# FMC_ADC_100M_10B_8CHA_TDC_PSU.net
KiCad netlist of a schematic drawn in Altium Designer
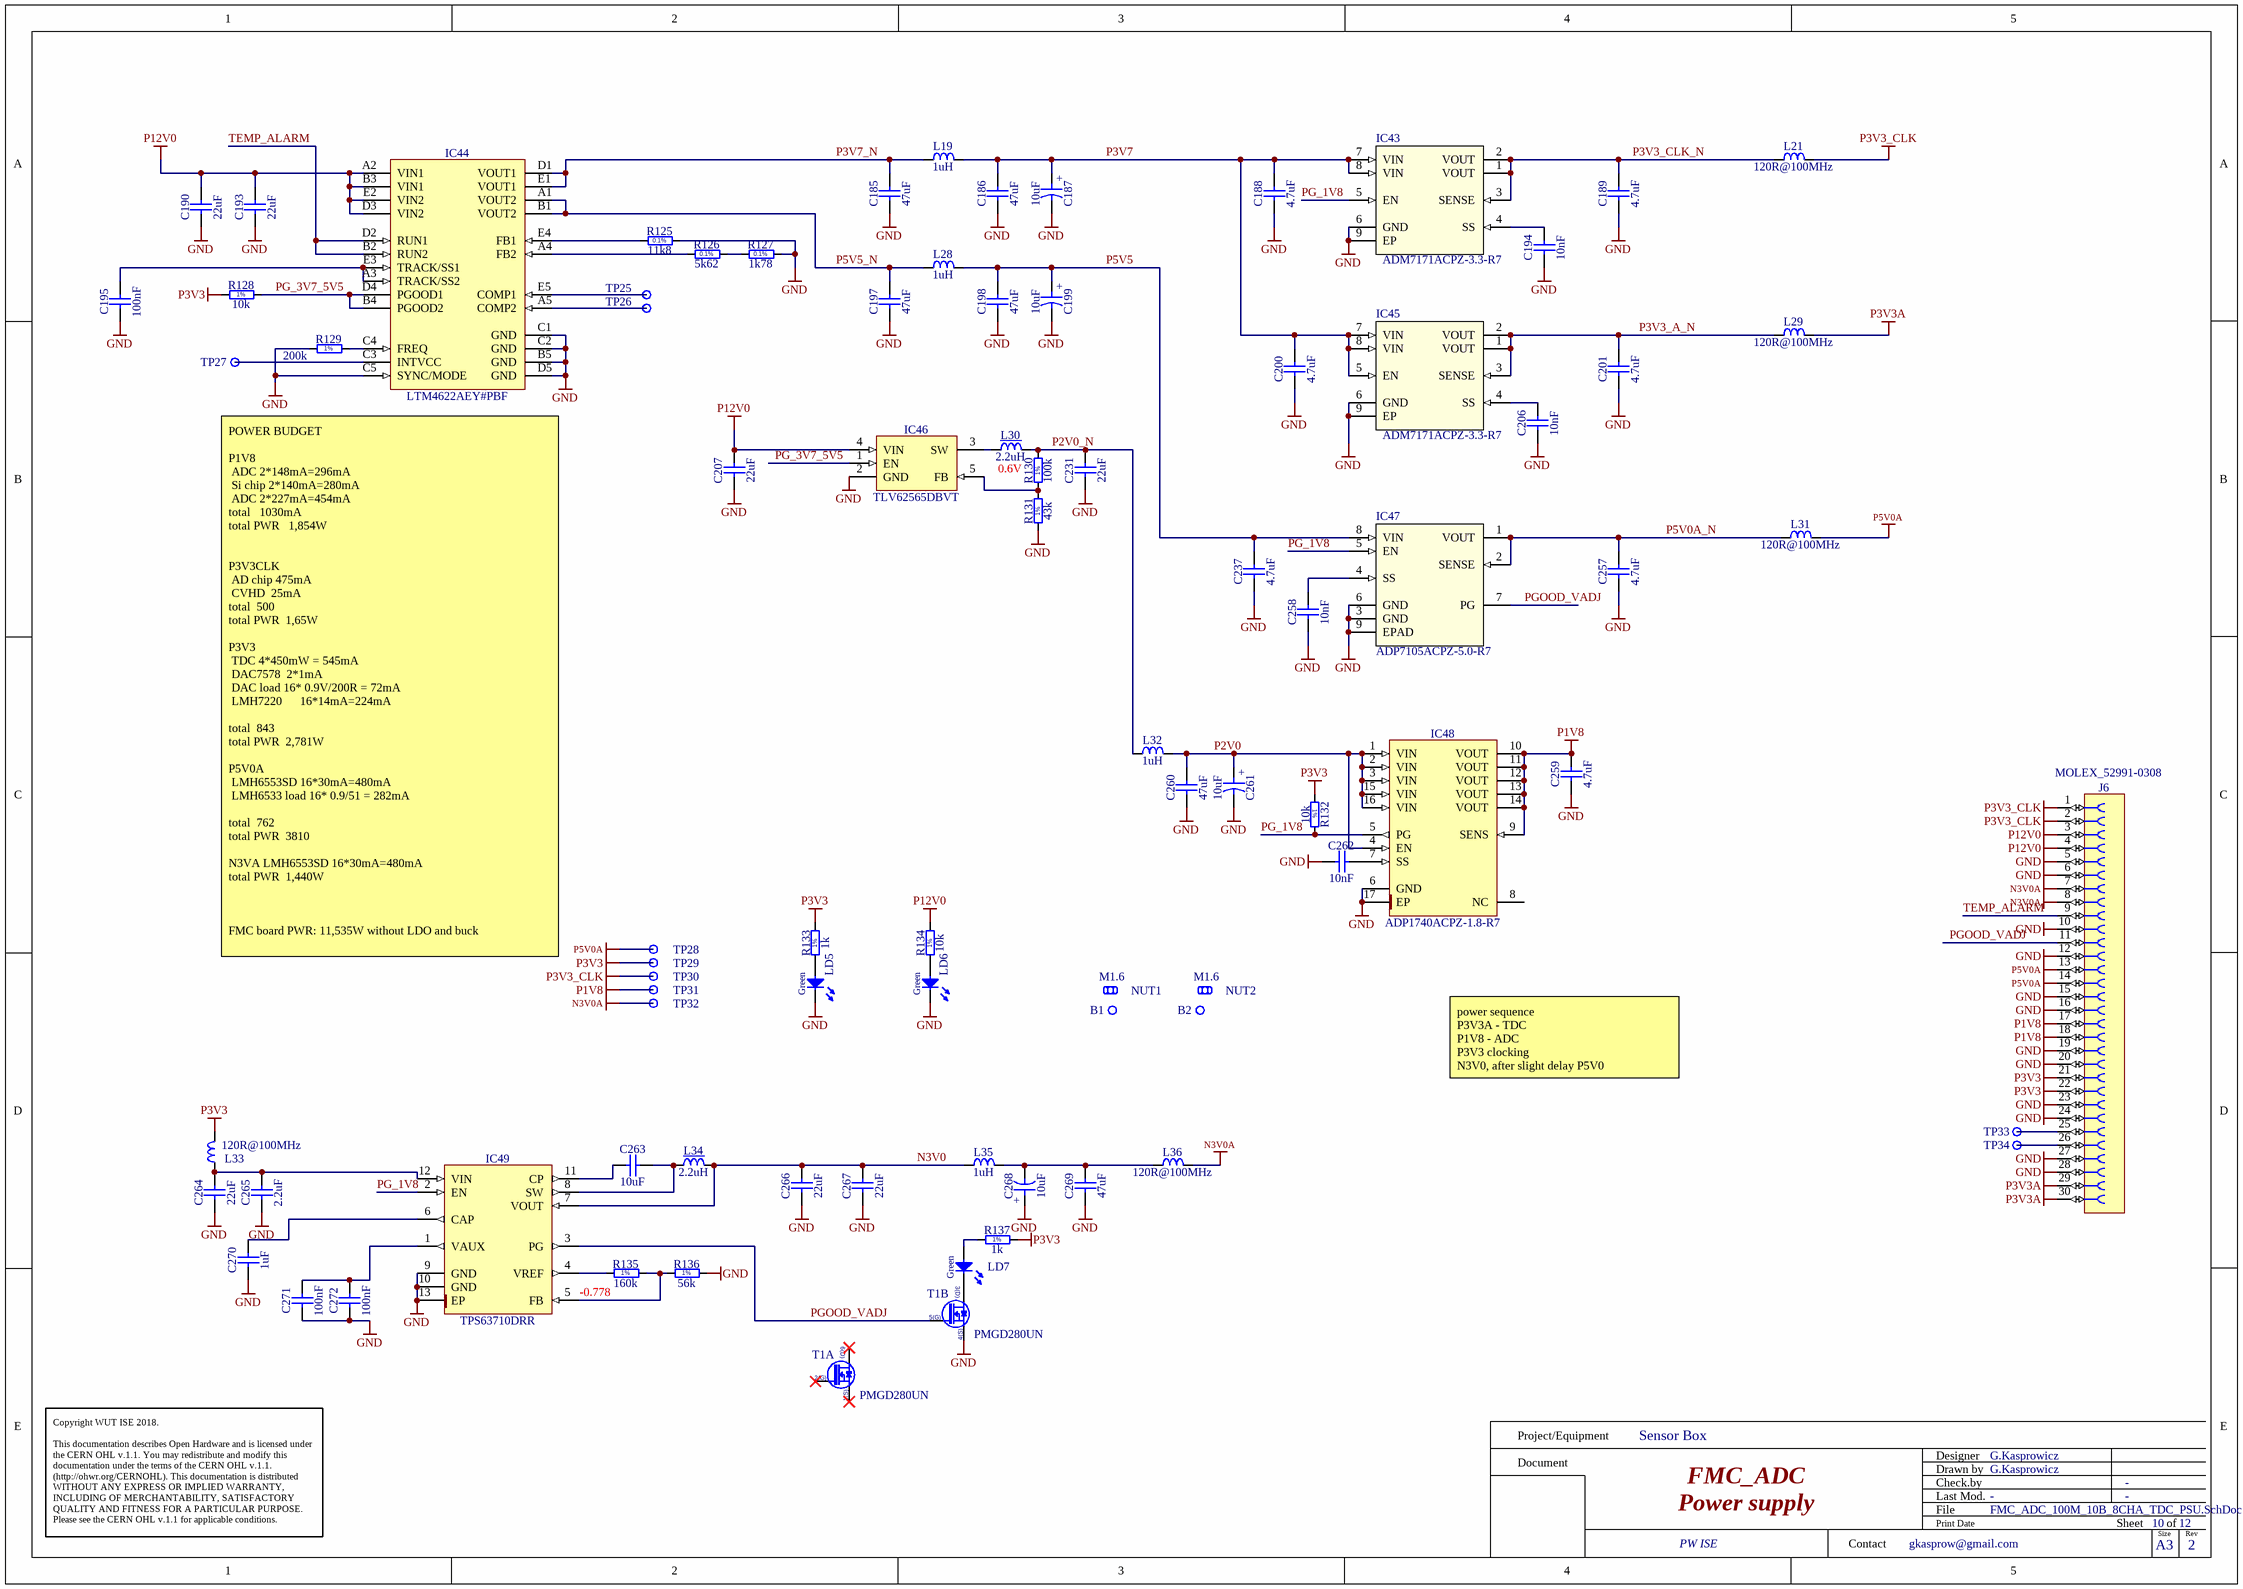
[diagram p0: FMC_ADC_100M_10B_8CHA_TDC_PSU.SchDoc]

(export (version "E")
  (design (tool "Eeschema 10.0.6"))
  (components
    (comp (ref "B1")
      (value "Plated Hole")
      (footprint "c300h160")
      (description "Single Terminal Socket")
      (fields (field (name "PART NUMBER") "PLATED_HOLE1.6_PAD3.0") (field (name "AUTHOR") "CERN DEM JMW"))
      (libsource (lib "Eletro-mechanical") (part "Single Terminal Socket"))
    )
    (comp (ref "B2")
      (value "Plated Hole")
      (footprint "c300h160")
      (description "Single Terminal Socket")
      (fields (field (name "PART NUMBER") "PLATED_HOLE1.6_PAD3.0") (field (name "AUTHOR") "CERN DEM JMW"))
      (libsource (lib "Eletro-mechanical") (part "Single Terminal Socket"))
    )
    (comp (ref "C185")
      (value "47uF")
      (footprint "CAPC2012X140N")
      (description "Non-polarised capacitor")
      (fields
        (field (name "PART NUMBER") "CC0805_47UF_6.3V_20%_X5R")
        (field (name "VOLTAGE") "6.3V")
        (field (name "AUTHOR") "CERN DEM JLC")
      )
      (libsource (lib "Capacitors") (part "Capacitor - non polarized"))
    )
    (comp (ref "C186")
      (value "47uF")
      (footprint "CAPC2012X140N")
      (description "Non-polarised capacitor")
      (fields
        (field (name "PART NUMBER") "CC0805_47UF_6.3V_20%_X5R")
        (field (name "VOLTAGE") "6.3V")
        (field (name "AUTHOR") "CERN DEM JLC")
      )
      (libsource (lib "Capacitors") (part "Capacitor - non polarized"))
    )
    (comp (ref "C187")
      (value "10uF")
      (footprint "CAPMP3216X180N")
      (description "Polarised capacitor")
      (fields
        (field (name "PART NUMBER") "CTE3216-18_10UF_10V_10%_LESR1800")
        (field (name "VOLTAGE") "10V")
        (field (name "AUTHOR") "CERN DEM JLC")
      )
      (libsource (lib "Capacitors") (part "Capacitor - polarized"))
    )
    (comp (ref "C188")
      (value "4.7uF")
      (footprint "CAPC1709X95N")
      (description "Non-polarised capacitor")
      (fields
        (field (name "PART NUMBER") "CC0603_4.7UF_16V_10%_X5R")
        (field (name "VOLTAGE") "16V")
        (field (name "AUTHOR") "CERN DEM JLC")
      )
      (libsource (lib "Capacitors") (part "Capacitor - non polarized"))
    )
    (comp (ref "C189")
      (value "4.7uF")
      (footprint "CAPC1709X95N")
      (description "Non-polarised capacitor")
      (fields
        (field (name "PART NUMBER") "CC0603_4.7UF_16V_10%_X5R")
        (field (name "VOLTAGE") "16V")
        (field (name "AUTHOR") "CERN DEM JLC")
      )
      (libsource (lib "Capacitors") (part "Capacitor - non polarized"))
    )
    (comp (ref "C190")
      (value "22uF")
      (footprint "CAPC2012X135N")
      (description "Non-polarised capacitor")
      (fields
        (field (name "PART NUMBER") "CC0805_22UF_16V_10%_X5R")
        (field (name "VOLTAGE") "16V")
        (field (name "AUTHOR") "CERN DEM JLC")
      )
      (libsource (lib "Capacitors") (part "Capacitor - non polarized"))
    )
    (comp (ref "C193")
      (value "22uF")
      (footprint "CAPC2012X135N")
      (description "Non-polarised capacitor")
      (fields
        (field (name "PART NUMBER") "CC0805_22UF_16V_10%_X5R")
        (field (name "VOLTAGE") "16V")
        (field (name "AUTHOR") "CERN DEM JLC")
      )
      (libsource (lib "Capacitors") (part "Capacitor - non polarized"))
    )
    (comp (ref "C194")
      (value "10nF")
      (footprint "CAPC1005X55N")
      (description "Non-polarised capacitor")
      (fields
        (field (name "PART NUMBER") "CC0402_10NF_16V_10%_X7R")
        (field (name "VOLTAGE") "16V")
        (field (name "AUTHOR") "CERN DEM JLC")
      )
      (libsource (lib "Capacitors") (part "Capacitor - non polarized"))
    )
    (comp (ref "C195")
      (value "100nF")
      (footprint "CAPC1005X55N")
      (description "Non-polarised capacitor")
      (fields
        (field (name "PART NUMBER") "CC0402_100NF_16V_10%_X5R")
        (field (name "VOLTAGE") "16V")
        (field (name "AUTHOR") "CERN DEM JLC")
      )
      (libsource (lib "Capacitors") (part "Capacitor - non polarized"))
    )
    (comp (ref "C197")
      (value "47uF")
      (footprint "CAPC2012X140N")
      (description "Non-polarised capacitor")
      (fields
        (field (name "PART NUMBER") "CC0805_47UF_6.3V_20%_X5R")
        (field (name "VOLTAGE") "6.3V")
        (field (name "AUTHOR") "CERN DEM JLC")
      )
      (libsource (lib "Capacitors") (part "Capacitor - non polarized"))
    )
    (comp (ref "C198")
      (value "47uF")
      (footprint "CAPC2012X140N")
      (description "Non-polarised capacitor")
      (fields
        (field (name "PART NUMBER") "CC0805_47UF_6.3V_20%_X5R")
        (field (name "VOLTAGE") "6.3V")
        (field (name "AUTHOR") "CERN DEM JLC")
      )
      (libsource (lib "Capacitors") (part "Capacitor - non polarized"))
    )
    (comp (ref "C199")
      (value "10uF")
      (footprint "CAPMP3216X180N")
      (description "Polarised capacitor")
      (fields
        (field (name "PART NUMBER") "CTE3216-18_10UF_10V_10%_LESR1800")
        (field (name "VOLTAGE") "10V")
        (field (name "AUTHOR") "CERN DEM JLC")
      )
      (libsource (lib "Capacitors") (part "Capacitor - polarized"))
    )
    (comp (ref "C200")
      (value "4.7uF")
      (footprint "CAPC1709X95N")
      (description "Non-polarised capacitor")
      (fields
        (field (name "PART NUMBER") "CC0603_4.7UF_16V_10%_X5R")
        (field (name "VOLTAGE") "16V")
        (field (name "AUTHOR") "CERN DEM JLC")
      )
      (libsource (lib "Capacitors") (part "Capacitor - non polarized"))
    )
    (comp (ref "C201")
      (value "4.7uF")
      (footprint "CAPC1709X95N")
      (description "Non-polarised capacitor")
      (fields
        (field (name "PART NUMBER") "CC0603_4.7UF_16V_10%_X5R")
        (field (name "VOLTAGE") "16V")
        (field (name "AUTHOR") "CERN DEM JLC")
      )
      (libsource (lib "Capacitors") (part "Capacitor - non polarized"))
    )
    (comp (ref "C206")
      (value "10nF")
      (footprint "CAPC1005X55N")
      (description "Non-polarised capacitor")
      (fields
        (field (name "PART NUMBER") "CC0402_10NF_16V_10%_X7R")
        (field (name "VOLTAGE") "16V")
        (field (name "AUTHOR") "CERN DEM JLC")
      )
      (libsource (lib "Capacitors") (part "Capacitor - non polarized"))
    )
    (comp (ref "C207")
      (value "22uF")
      (footprint "CAPC2012X135N")
      (description "Non-polarised capacitor")
      (fields
        (field (name "PART NUMBER") "CC0805_22UF_16V_10%_X5R")
        (field (name "VOLTAGE") "16V")
        (field (name "AUTHOR") "CERN DEM JLC")
      )
      (libsource (lib "Capacitors") (part "Capacitor - non polarized"))
    )
    (comp (ref "C231")
      (value "22uF")
      (footprint "CAPC2012X135N")
      (description "Non-polarised capacitor")
      (fields
        (field (name "PART NUMBER") "CC0805_22UF_16V_10%_X5R")
        (field (name "VOLTAGE") "16V")
        (field (name "AUTHOR") "CERN DEM JLC")
      )
      (libsource (lib "Capacitors") (part "Capacitor - non polarized"))
    )
    (comp (ref "C237")
      (value "4.7uF")
      (footprint "CAPC1709X95N")
      (description "Non-polarised capacitor")
      (fields
        (field (name "PART NUMBER") "CC0603_4.7UF_16V_10%_X5R")
        (field (name "VOLTAGE") "16V")
        (field (name "AUTHOR") "CERN DEM JLC")
      )
      (libsource (lib "Capacitors") (part "Capacitor - non polarized"))
    )
    (comp (ref "C257")
      (value "4.7uF")
      (footprint "CAPC1709X95N")
      (description "Non-polarised capacitor")
      (fields
        (field (name "PART NUMBER") "CC0603_4.7UF_16V_10%_X5R")
        (field (name "VOLTAGE") "16V")
        (field (name "AUTHOR") "CERN DEM JLC")
      )
      (libsource (lib "Capacitors") (part "Capacitor - non polarized"))
    )
    (comp (ref "C258")
      (value "10nF")
      (footprint "CAPC1005X55N")
      (description "Non-polarised capacitor")
      (fields
        (field (name "PART NUMBER") "CC0402_10NF_16V_10%_X7R")
        (field (name "VOLTAGE") "16V")
        (field (name "AUTHOR") "CERN DEM JLC")
      )
      (libsource (lib "Capacitors") (part "Capacitor - non polarized"))
    )
    (comp (ref "C259")
      (value "4.7uF")
      (footprint "CAPC1709X95N")
      (description "Non-polarised capacitor")
      (fields
        (field (name "PART NUMBER") "CC0603_4.7UF_16V_10%_X5R")
        (field (name "VOLTAGE") "16V")
        (field (name "AUTHOR") "CERN DEM JLC")
      )
      (libsource (lib "Capacitors") (part "Capacitor - non polarized"))
    )
    (comp (ref "C260")
      (value "47uF")
      (footprint "CAPC2012X140N")
      (description "Non-polarised capacitor")
      (fields
        (field (name "PART NUMBER") "CC0805_47UF_6.3V_20%_X5R")
        (field (name "VOLTAGE") "6.3V")
        (field (name "AUTHOR") "CERN DEM JLC")
      )
      (libsource (lib "Capacitors") (part "Capacitor - non polarized"))
    )
    (comp (ref "C261")
      (value "10uF")
      (footprint "CAPMP3216X180N")
      (description "Polarised capacitor")
      (fields
        (field (name "PART NUMBER") "CTE3216-18_10UF_10V_10%_LESR1800")
        (field (name "VOLTAGE") "10V")
        (field (name "AUTHOR") "CERN DEM JLC")
      )
      (libsource (lib "Capacitors") (part "Capacitor - polarized"))
    )
    (comp (ref "C262")
      (value "10nF")
      (footprint "CAPC1005X55N")
      (description "Non-polarised capacitor")
      (fields
        (field (name "PART NUMBER") "CC0402_10NF_16V_10%_X7R")
        (field (name "VOLTAGE") "16V")
        (field (name "AUTHOR") "CERN DEM JLC")
      )
      (libsource (lib "Capacitors") (part "Capacitor - non polarized"))
    )
    (comp (ref "C263")
      (value "10uF")
      (footprint "CAPC2012X135N")
      (description "Non-polarised capacitor")
      (fields
        (field (name "PART NUMBER") "CC0805_10UF_16V_10%_X5R")
        (field (name "VOLTAGE") "16V")
        (field (name "AUTHOR") "CERN DEM JLC")
      )
      (libsource (lib "Capacitors") (part "Capacitor - non polarized"))
    )
    (comp (ref "C264")
      (value "22uF")
      (footprint "CAPC2012X135N")
      (description "Non-polarised capacitor")
      (fields
        (field (name "PART NUMBER") "CC0805_22UF_16V_10%_X5R")
        (field (name "VOLTAGE") "16V")
        (field (name "AUTHOR") "CERN DEM JLC")
      )
      (libsource (lib "Capacitors") (part "Capacitor - non polarized"))
    )
    (comp (ref "C265")
      (value "2.2uF")
      (footprint "CAPC1608X87N")
      (description "Non-polarised capacitor")
      (fields
        (field (name "PART NUMBER") "CC0603_2.2UF_16V_10%_X5R")
        (field (name "VOLTAGE") "16V")
        (field (name "AUTHOR") "CERN DEM JLC")
      )
      (libsource (lib "Capacitors") (part "Capacitor - non polarized"))
    )
    (comp (ref "C266")
      (value "22uF")
      (footprint "CAPC2012X135N")
      (description "Non-polarised capacitor")
      (fields
        (field (name "PART NUMBER") "CC0805_22UF_16V_10%_X5R")
        (field (name "VOLTAGE") "16V")
        (field (name "AUTHOR") "CERN DEM JLC")
      )
      (libsource (lib "Capacitors") (part "Capacitor - non polarized"))
    )
    (comp (ref "C267")
      (value "22uF")
      (footprint "CAPC2012X135N")
      (description "Non-polarised capacitor")
      (fields
        (field (name "PART NUMBER") "CC0805_22UF_16V_10%_X5R")
        (field (name "VOLTAGE") "16V")
        (field (name "AUTHOR") "CERN DEM JLC")
      )
      (libsource (lib "Capacitors") (part "Capacitor - non polarized"))
    )
    (comp (ref "C268")
      (value "10uF")
      (footprint "CAPMP3216X180N")
      (description "Polarised capacitor")
      (fields
        (field (name "PART NUMBER") "CTE3216-18_10UF_10V_10%_LESR1800")
        (field (name "VOLTAGE") "10V")
        (field (name "AUTHOR") "CERN DEM JLC")
      )
      (libsource (lib "Capacitors") (part "Capacitor - polarized"))
    )
    (comp (ref "C269")
      (value "47uF")
      (footprint "CAPC2012X140N")
      (description "Non-polarised capacitor")
      (fields
        (field (name "PART NUMBER") "CC0805_47UF_6.3V_20%_X5R")
        (field (name "VOLTAGE") "6.3V")
        (field (name "AUTHOR") "CERN DEM JLC")
      )
      (libsource (lib "Capacitors") (part "Capacitor - non polarized"))
    )
    (comp (ref "C270")
      (value "1uF")
      (footprint "CAPC1608X87N")
      (description "Non-polarised capacitor")
      (fields
        (field (name "PART NUMBER") "CC0603_1UF_16V_10%_X7R")
        (field (name "VOLTAGE") "16V")
        (field (name "AUTHOR") "CERN DEM JLC")
      )
      (libsource (lib "Capacitors") (part "Capacitor - non polarized"))
    )
    (comp (ref "C271")
      (value "100nF")
      (footprint "CAPC1005X55N")
      (description "Non-polarised capacitor")
      (fields
        (field (name "PART NUMBER") "CC0402_100NF_16V_10%_X5R")
        (field (name "VOLTAGE") "16V")
        (field (name "AUTHOR") "CERN DEM JLC")
      )
      (libsource (lib "Capacitors") (part "Capacitor - non polarized"))
    )
    (comp (ref "C272")
      (value "100nF")
      (footprint "CAPC1005X55N")
      (description "Non-polarised capacitor")
      (fields
        (field (name "PART NUMBER") "CC0402_100NF_16V_10%_X5R")
        (field (name "VOLTAGE") "16V")
        (field (name "AUTHOR") "CERN DEM JLC")
      )
      (libsource (lib "Capacitors") (part "Capacitor - non polarized"))
    )
    (comp (ref "IC43")
      (value "ADM7171ACPZ-3.3-R7")
      (footprint "CP_8_21-L")
      (description "6.5 V, 1 A, Ultralow Noise, High PSRR,  Fast Transient Response CMOS LDO")
      (fields (field (name "MANUFACTURER") "Analog Devices"))
      (libsource (lib "FMC_ADC") (part "ADM7171ACPZ-3.3-R7"))
    )
    (comp (ref "IC44")
      (value "LTM4622AEY#PBF")
      (footprint "BGA25C127P5X5_625X625X262")
      (description "3.6V-20V To 1.5V-12V, Dual 2A or Single 4A  Ultrathin Step-Down DC/DC µModule Regulator")
      (fields (field (name "MANUFACTURER") "LINEAR TECHNOLOGY") (field (name "AUTHOR") "CERN DEM MR"))
      (libsource (lib "ICs And Semiconductors") (part "LTM4622A"))
    )
    (comp (ref "IC45")
      (value "ADM7171ACPZ-3.3-R7")
      (footprint "CP_8_21-L")
      (description "6.5 V, 1 A, Ultralow Noise, High PSRR,  Fast Transient Response CMOS LDO")
      (fields (field (name "MANUFACTURER") "Analog Devices"))
      (libsource (lib "FMC_ADC") (part "ADM7171ACPZ-3.3-R7"))
    )
    (comp (ref "IC46")
      (value "TLV62565DBVT")
      (footprint "SOT95P280X145-5N")
      (description "1.5A High Efficiency Step-Down Converter, Adjustable Output Voltage")
      (fields (field (name "MANUFACTURER") "TEXAS INSTRUMENTS") (field (name "AUTHOR") "CERN DEM JMW"))
      (libsource (lib "ICs And Semiconductors") (part "TLV62565"))
    )
    (comp (ref "IC47")
      (value "ADP7105ACPZ-5.0-R7")
      (footprint "CP_8_5")
      (description "20 V, 500 mA, Low Noise LDO Regulator  with Soft Start")
      (fields (field (name "MANUFACTURER") "Analog Devices"))
      (libsource (lib "FMC_ADC") (part "ADP7105ACPZ-5.0-R7"))
    )
    (comp (ref "IC48")
      (value "ADP1740ACPZ-1.8-R7")
      (footprint "QFN65P400X400X100-17N-S225")
      (description "2A, Low-Dropout Linear Regulator")
      (fields (field (name "MANUFACTURER") "ANALOG DEVICES") (field (name "AUTHOR") "CERN DEM JLC"))
      (libsource (lib "ICs And Semiconductors") (part "ADP1740"))
    )
    (comp (ref "IC49")
      (value "TPS63710DRR")
      (footprint "SON50P300X300X80-13N-R160X260")
      (description "-1 to -5.5VDC, 1A Output, Low Noise Synchronous Inverting Buck Converter")
      (fields (field (name "MANUFACTURER") "TEXAS INSTRUMENTS") (field (name "AUTHOR") "CERN DEM BC"))
      (libsource (lib "ICs And Semiconductors") (part "TPS63710"))
    )
    (comp (ref "J6")
      (value "SlimStack™")
      (footprint "MOLEX_52991-0308")
      (description "Connector 30 Female")
      (fields
        (field (name "PART NUMBER") "MOLEX_52991-0308")
        (field (name "MANUFACTURER") "MOLEX")
        (field (name "MANUFACTURER PART NUMBER") "52991-0308")
        (field (name "AUTHOR") "CERN DEM JLC")
      )
      (libsource (lib "Connectors") (part "Connector 30 Female"))
    )
    (comp (ref "L19")
      (value "1uH")
      (footprint "INDC2620X100N")
      (description "Inductor")
      (fields
        (field (name "PART NUMBER") "IND1008_1UH_20%_WURTH_74479787210B")
        (field (name "POWER") "1.95A")
        (field (name "AUTHOR") "CERN DEM JLC")
      )
      (libsource (lib "") (part "Inductor_1"))
    )
    (comp (ref "L21")
      (value "120R@100MHz")
      (footprint "INDC1608X65N")
      (description "Inductor")
      (fields
        (field (name "PART NUMBER") "IND0603_MURATA_BLM18SG121TN1D")
        (field (name "POWER") "3A")
        (field (name "AUTHOR") "CERN DEM JLC")
      )
      (libsource (lib "") (part "Inductor_1"))
    )
    (comp (ref "L28")
      (value "1uH")
      (footprint "INDC2620X100N")
      (description "Inductor")
      (fields
        (field (name "PART NUMBER") "IND1008_1UH_20%_WURTH_74479787210B")
        (field (name "POWER") "1.95A")
        (field (name "AUTHOR") "CERN DEM JLC")
      )
      (libsource (lib "") (part "Inductor_1"))
    )
    (comp (ref "L29")
      (value "120R@100MHz")
      (footprint "INDC1608X65N")
      (description "Inductor")
      (fields
        (field (name "PART NUMBER") "IND0603_MURATA_BLM18SG121TN1D")
        (field (name "POWER") "3A")
        (field (name "AUTHOR") "CERN DEM JLC")
      )
      (libsource (lib "") (part "Inductor_1"))
    )
    (comp (ref "L30")
      (value "2.2uH")
      (footprint "IND_WURTH_WE-TPC_4828")
      (description "Inductor With Core")
      (fields
        (field (name "PART NUMBER") "IND_2.2UH_30%_WURTH_WE-TPC_7440430022")
        (field (name "POWER") "2.5A")
        (field (name "AUTHOR") "CERN DEM JLC")
      )
      (libsource (lib "Inductors & Transformers") (part "Inductor With Magnetic core"))
    )
    (comp (ref "L31")
      (value "120R@100MHz")
      (footprint "INDC1608X65N")
      (description "Inductor")
      (fields
        (field (name "PART NUMBER") "IND0603_MURATA_BLM18SG121TN1D")
        (field (name "POWER") "3A")
        (field (name "AUTHOR") "CERN DEM JLC")
      )
      (libsource (lib "") (part "Inductor_1"))
    )
    (comp (ref "L32")
      (value "1uH")
      (footprint "INDC2620X100N")
      (description "Inductor")
      (fields
        (field (name "PART NUMBER") "IND1008_1UH_20%_WURTH_74479787210B")
        (field (name "POWER") "1.95A")
        (field (name "AUTHOR") "CERN DEM JLC")
      )
      (libsource (lib "") (part "Inductor_1"))
    )
    (comp (ref "L33")
      (value "120R@100MHz")
      (footprint "INDC1608X65N")
      (description "Inductor")
      (fields
        (field (name "PART NUMBER") "IND0603_MURATA_BLM18SG121TN1D")
        (field (name "POWER") "3A")
        (field (name "AUTHOR") "CERN DEM JLC")
      )
      (libsource (lib "Inductors & Transformers") (part "Inductor"))
    )
    (comp (ref "L34")
      (value "2.2uH")
      (footprint "IND_WURTH_WE-TPC_4828")
      (description "Inductor With Core")
      (fields
        (field (name "PART NUMBER") "IND_2.2UH_30%_WURTH_WE-TPC_7440430022")
        (field (name "POWER") "2.5A")
        (field (name "AUTHOR") "CERN DEM JLC")
      )
      (libsource (lib "Inductors & Transformers") (part "Inductor With Magnetic core"))
    )
    (comp (ref "L35")
      (value "1uH")
      (footprint "INDC2620X100N")
      (description "Inductor")
      (fields
        (field (name "PART NUMBER") "IND1008_1UH_20%_WURTH_74479787210B")
        (field (name "POWER") "1.95A")
        (field (name "AUTHOR") "CERN DEM JLC")
      )
      (libsource (lib "") (part "Inductor_1"))
    )
    (comp (ref "L36")
      (value "120R@100MHz")
      (footprint "INDC1608X65N")
      (description "Inductor")
      (fields
        (field (name "PART NUMBER") "IND0603_MURATA_BLM18SG121TN1D")
        (field (name "POWER") "3A")
        (field (name "AUTHOR") "CERN DEM JLC")
      )
      (libsource (lib "") (part "Inductor_1"))
    )
    (comp (ref "LD5")
      (value "Green")
      (footprint "LED_KINGBRIGHT_KPH-1608CGCK")
      (description "LED Green 1C 2A")
      (fields
        (field (name "PART NUMBER") "LED_KINGBRIGHT_KPH-1608CGCK")
        (field (name "MANUFACTURER") "KINGBRIGHT")
        (field (name "AUTHOR") "CERN DEM JLC")
      )
      (libsource (lib "ICs And Semiconductors") (part "LED Green 1C 2A"))
    )
    (comp (ref "LD6")
      (value "Green")
      (footprint "LED_KINGBRIGHT_KPH-1608CGCK")
      (description "LED Green 1C 2A")
      (fields
        (field (name "PART NUMBER") "LED_KINGBRIGHT_KPH-1608CGCK")
        (field (name "MANUFACTURER") "KINGBRIGHT")
        (field (name "AUTHOR") "CERN DEM JLC")
      )
      (libsource (lib "ICs And Semiconductors") (part "LED Green 1C 2A"))
    )
    (comp (ref "LD7")
      (value "Green")
      (footprint "LED_KINGBRIGHT_KPH-1608CGCK")
      (description "LED Green 1C 2A")
      (fields
        (field (name "PART NUMBER") "LED_KINGBRIGHT_KPH-1608CGCK")
        (field (name "MANUFACTURER") "KINGBRIGHT")
        (field (name "AUTHOR") "CERN DEM JLC")
      )
      (libsource (lib "ICs And Semiconductors") (part "LED Green 1C 2A"))
    )
    (comp (ref "NUT1")
      (value "M1.6")
      (footprint "BOSSARD_BN628-1241389_v")
      (description "Nut")
      (fields
        (field (name "PART NUMBER") "BOSSARD_BN628-1241389_v")
        (field (name "MANUFACTURER") "BOSSARD")
        (field (name "AUTHOR") "CERN DEM JMW")
      )
      (libsource (lib "Eletro-mechanical") (part "Nut"))
    )
    (comp (ref "NUT2")
      (value "M1.6")
      (footprint "BOSSARD_BN628-1241389_v")
      (description "Nut")
      (fields
        (field (name "PART NUMBER") "BOSSARD_BN628-1241389_v")
        (field (name "MANUFACTURER") "BOSSARD")
        (field (name "AUTHOR") "CERN DEM JMW")
      )
      (libsource (lib "Eletro-mechanical") (part "Nut"))
    )
    (comp (ref "R125")
      (value "11k8")
      (footprint "RESC1608X55N")
      (description "Resistor - 0.1%")
      (fields
        (field (name "PART NUMBER") "R0603_11K8_0.1%_0.063W_10PPM")
        (field (name "POWER") "0.063W")
        (field (name "AUTHOR") "CERN DEM JLC")
      )
      (libsource (lib "Resistors") (part "Resistor - 0.1%"))
    )
    (comp (ref "R126")
      (value "5k62")
      (footprint "RESC1608X55N")
      (description "Resistor - 0.1%")
      (fields
        (field (name "PART NUMBER") "R0603_5K62_0.1%_0.063W_10PPM")
        (field (name "POWER") "0.063W")
        (field (name "AUTHOR") "CERN DEM JLC")
      )
      (libsource (lib "Resistors") (part "Resistor - 0.1%"))
    )
    (comp (ref "R127")
      (value "1k78")
      (footprint "RESC1608X55N")
      (description "Resistor - 0.1%")
      (fields
        (field (name "PART NUMBER") "R0603_1K78_0.1%_0.063W_10PPM")
        (field (name "POWER") "0.063W")
        (field (name "AUTHOR") "CERN DEM JLC")
      )
      (libsource (lib "Resistors") (part "Resistor - 0.1%"))
    )
    (comp (ref "R128")
      (value "10k")
      (footprint "RESC1005X40N")
      (description "Resistor - 1%")
      (fields
        (field (name "PART NUMBER") "R0402_10K_1%_0.0625W_100PPM")
        (field (name "POWER") "0.0625W")
        (field (name "AUTHOR") "CERN DEM JLC")
      )
      (libsource (lib "Resistors") (part "Resistor - 1%"))
    )
    (comp (ref "R129")
      (value "200k")
      (footprint "RESC1005X40N")
      (description "Resistor - 1%")
      (fields
        (field (name "PART NUMBER") "R0402_200K_1%_0.0625W_100PPM")
        (field (name "POWER") "0.0625W")
        (field (name "AUTHOR") "CERN DEM JLC")
      )
      (libsource (lib "Resistors") (part "Resistor - 1%"))
    )
    (comp (ref "R130")
      (value "100k")
      (footprint "RESC1005X40N")
      (description "Resistor - 1%")
      (fields
        (field (name "PART NUMBER") "R0402_100K_1%_0.0625W_100PPM")
        (field (name "POWER") "0.0625W")
        (field (name "AUTHOR") "CERN DEM JLC")
      )
      (libsource (lib "Resistors") (part "Resistor - 1%"))
    )
    (comp (ref "R131")
      (value "43k")
      (footprint "RESC1005X40N")
      (description "Resistor - 1%")
      (fields
        (field (name "PART NUMBER") "R0402_43K_1%_0.0625W_100PPM")
        (field (name "POWER") "0.0625W")
        (field (name "AUTHOR") "CERN DEM JLC")
      )
      (libsource (lib "Resistors") (part "Resistor - 1%"))
    )
    (comp (ref "R132")
      (value "10k")
      (footprint "RESC1005X40N")
      (description "Resistor - 1%")
      (fields
        (field (name "PART NUMBER") "R0402_10K_1%_0.0625W_100PPM")
        (field (name "POWER") "0.0625W")
        (field (name "AUTHOR") "CERN DEM JLC")
      )
      (libsource (lib "Resistors") (part "Resistor - 1%"))
    )
    (comp (ref "R133")
      (value "1k")
      (footprint "RESC1005X40N")
      (description "Resistor - 1%")
      (fields
        (field (name "PART NUMBER") "R0402_1K_1%_0.0625W_100PPM")
        (field (name "POWER") "0.0625W")
        (field (name "AUTHOR") "CERN DEM JLC")
      )
      (libsource (lib "Resistors") (part "Resistor - 1%"))
    )
    (comp (ref "R134")
      (value "10k")
      (footprint "RESC1005X40N")
      (description "Resistor - 1%")
      (fields
        (field (name "PART NUMBER") "R0402_10K_1%_0.0625W_100PPM")
        (field (name "POWER") "0.0625W")
        (field (name "AUTHOR") "CERN DEM JLC")
      )
      (libsource (lib "Resistors") (part "Resistor - 1%"))
    )
    (comp (ref "R135")
      (value "160k")
      (footprint "RESC1005X40N")
      (description "Resistor - 1%")
      (fields
        (field (name "PART NUMBER") "R0402_160K_1%_0.0625W_100PPM")
        (field (name "POWER") "0.0625W")
        (field (name "AUTHOR") "CERN DEM JLC")
      )
      (libsource (lib "Resistors") (part "Resistor - 1%"))
    )
    (comp (ref "R136")
      (value "56k")
      (footprint "RESC1005X40N")
      (description "Resistor - 1%")
      (fields
        (field (name "PART NUMBER") "R0402_56K_1%_0.0625W_100PPM")
        (field (name "POWER") "0.0625W")
        (field (name "AUTHOR") "CERN DEM JLC")
      )
      (libsource (lib "Resistors") (part "Resistor - 1%"))
    )
    (comp (ref "R137")
      (value "1k")
      (footprint "RESC1005X40N")
      (description "Resistor - 1%")
      (fields
        (field (name "PART NUMBER") "R0402_1K_1%_0.0625W_100PPM")
        (field (name "POWER") "0.0625W")
        (field (name "AUTHOR") "CERN DEM JLC")
      )
      (libsource (lib "Resistors") (part "Resistor - 1%"))
    )
    (comp (ref "T1")
      (value "PMGD280UN")
      (footprint "SOT65P210X110-6N")
      (description "Dual N-Channel micro TrenchMOS™ Ultra Low Level FET")
      (fields (field (name "MANUFACTURER") "NXP SEMICONDUCTORS") (field (name "AUTHOR") "CERN DEM JLC"))
      (libsource (lib "") (part "PMGD280UN_1"))
    )
    (comp (ref "TP25")
      (value "Test Point")
      (footprint "TPS127")
      (fields (field (name "PART NUMBER") "SMD_PAD_1.27X1.27MM") (field (name "AUTHOR") "CERN DEM JLC"))
      (libsource (lib "Eletro-mechanical") (part "Test Point"))
    )
    (comp (ref "TP26")
      (value "Test Point")
      (footprint "TPS127")
      (fields (field (name "PART NUMBER") "SMD_PAD_1.27X1.27MM") (field (name "AUTHOR") "CERN DEM JLC"))
      (libsource (lib "Eletro-mechanical") (part "Test Point"))
    )
    (comp (ref "TP27")
      (value "Test Point")
      (footprint "TPS127")
      (fields (field (name "PART NUMBER") "SMD_PAD_1.27X1.27MM") (field (name "AUTHOR") "CERN DEM JLC"))
      (libsource (lib "Eletro-mechanical") (part "Test Point"))
    )
    (comp (ref "TP28")
      (value "Test Point")
      (footprint "TPS127")
      (fields (field (name "PART NUMBER") "SMD_PAD_1.27X1.27MM") (field (name "AUTHOR") "CERN DEM JLC"))
      (libsource (lib "Eletro-mechanical") (part "Test Point"))
    )
    (comp (ref "TP29")
      (value "Test Point")
      (footprint "TPS127")
      (fields (field (name "PART NUMBER") "SMD_PAD_1.27X1.27MM") (field (name "AUTHOR") "CERN DEM JLC"))
      (libsource (lib "Eletro-mechanical") (part "Test Point"))
    )
    (comp (ref "TP30")
      (value "Test Point")
      (footprint "TPS127")
      (fields (field (name "PART NUMBER") "SMD_PAD_1.27X1.27MM") (field (name "AUTHOR") "CERN DEM JLC"))
      (libsource (lib "Eletro-mechanical") (part "Test Point"))
    )
    (comp (ref "TP31")
      (value "Test Point")
      (footprint "TPS127")
      (fields (field (name "PART NUMBER") "SMD_PAD_1.27X1.27MM") (field (name "AUTHOR") "CERN DEM JLC"))
      (libsource (lib "Eletro-mechanical") (part "Test Point"))
    )
    (comp (ref "TP32")
      (value "Test Point")
      (footprint "TPS127")
      (fields (field (name "PART NUMBER") "SMD_PAD_1.27X1.27MM") (field (name "AUTHOR") "CERN DEM JLC"))
      (libsource (lib "Eletro-mechanical") (part "Test Point"))
    )
    (comp (ref "TP33")
      (value "Test Point")
      (footprint "TPS127")
      (fields (field (name "PART NUMBER") "SMD_PAD_1.27X1.27MM") (field (name "AUTHOR") "CERN DEM JLC"))
      (libsource (lib "Eletro-mechanical") (part "Test Point"))
    )
    (comp (ref "TP34")
      (value "Test Point")
      (footprint "TPS127")
      (fields (field (name "PART NUMBER") "SMD_PAD_1.27X1.27MM") (field (name "AUTHOR") "CERN DEM JLC"))
      (libsource (lib "Eletro-mechanical") (part "Test Point"))
    )
  )
  (nets
    (net (code "1") (name "/N3V0") (class "Default")
      (node (ref "C266") (pin "2") (pinfunction "2_2") (pintype "passive"))
      (node (ref "C267") (pin "2") (pinfunction "2_2") (pintype "passive"))
      (node (ref "IC49") (pin "7") (pinfunction "VOUT_7") (pintype "input"))
      (node (ref "L34") (pin "2") (pinfunction "2_2") (pintype "passive"))
      (node (ref "L35") (pin "1") (pinfunction "1_1") (pintype "passive"))
    )
    (net (code "2") (name "/P2V0") (class "Default")
      (node (ref "C260") (pin "2") (pinfunction "2_2") (pintype "passive"))
      (node (ref "C261") (pin "1") (pinfunction "1_1") (pintype "passive"))
      (node (ref "IC48") (pin "1") (pinfunction "VIN_1") (pintype "input"))
      (node (ref "IC48") (pin "15") (pinfunction "VIN_15") (pintype "input"))
      (node (ref "IC48") (pin "16") (pinfunction "VIN_16") (pintype "input"))
      (node (ref "IC48") (pin "2") (pinfunction "VIN_2") (pintype "input"))
      (node (ref "IC48") (pin "3") (pinfunction "VIN_3") (pintype "input"))
      (node (ref "IC48") (pin "4") (pinfunction "EN_4") (pintype "input"))
      (node (ref "L32") (pin "2") (pinfunction "2_2") (pintype "passive"))
    )
    (net (code "3") (name "/P2V0_N") (class "Default")
      (node (ref "C231") (pin "2") (pinfunction "2_2") (pintype "passive"))
      (node (ref "L30") (pin "2") (pinfunction "2_2") (pintype "passive"))
      (node (ref "L32") (pin "1") (pinfunction "1_1") (pintype "passive"))
      (node (ref "R130") (pin "2") (pinfunction "2_2") (pintype "passive"))
    )
    (net (code "4") (name "/P3V3_A_N") (class "Default")
      (node (ref "C201") (pin "2") (pinfunction "2_2") (pintype "passive"))
      (node (ref "IC45") (pin "1") (pinfunction "VOUT_1") (pintype "power_in"))
      (node (ref "IC45") (pin "2") (pinfunction "VOUT_2") (pintype "power_in"))
      (node (ref "IC45") (pin "3") (pinfunction "SENSE_3") (pintype "input"))
      (node (ref "L29") (pin "1") (pinfunction "1_1") (pintype "passive"))
    )
    (net (code "5") (name "/P3V3_CLK_N") (class "Default")
      (node (ref "C189") (pin "2") (pinfunction "2_2") (pintype "passive"))
      (node (ref "IC43") (pin "1") (pinfunction "VOUT_1") (pintype "power_in"))
      (node (ref "IC43") (pin "2") (pinfunction "VOUT_2") (pintype "power_in"))
      (node (ref "IC43") (pin "3") (pinfunction "SENSE_3") (pintype "input"))
      (node (ref "L21") (pin "1") (pinfunction "1_1") (pintype "passive"))
    )
    (net (code "6") (name "/P3V7") (class "Default")
      (node (ref "C186") (pin "2") (pinfunction "2_2") (pintype "passive"))
      (node (ref "C187") (pin "1") (pinfunction "1_1") (pintype "passive"))
      (node (ref "C188") (pin "2") (pinfunction "2_2") (pintype "passive"))
      (node (ref "C200") (pin "2") (pinfunction "2_2") (pintype "passive"))
      (node (ref "IC43") (pin "7") (pinfunction "VIN_7") (pintype "input"))
      (node (ref "IC43") (pin "8") (pinfunction "VIN_8") (pintype "input"))
      (node (ref "IC45") (pin "5") (pinfunction "EN_5") (pintype "input"))
      (node (ref "IC45") (pin "7") (pinfunction "VIN_7") (pintype "input"))
      (node (ref "IC45") (pin "8") (pinfunction "VIN_8") (pintype "input"))
      (node (ref "L19") (pin "2") (pinfunction "2_2") (pintype "passive"))
    )
    (net (code "7") (name "/P3V7_N") (class "Default")
      (node (ref "C185") (pin "2") (pinfunction "2_2") (pintype "passive"))
      (node (ref "IC44") (pin "D1") (pinfunction "VOUT1_D1") (pintype "power_in"))
      (node (ref "IC44") (pin "E1") (pinfunction "VOUT1_E1") (pintype "power_in"))
      (node (ref "L19") (pin "1") (pinfunction "1_1") (pintype "passive"))
    )
    (net (code "8") (name "/P5V0A_N") (class "Default")
      (node (ref "C257") (pin "2") (pinfunction "2_2") (pintype "passive"))
      (node (ref "IC47") (pin "1") (pinfunction "VOUT_1") (pintype "power_in"))
      (node (ref "IC47") (pin "2") (pinfunction "SENSE_2") (pintype "input"))
      (node (ref "L31") (pin "1") (pinfunction "1_1") (pintype "passive"))
    )
    (net (code "9") (name "/P5V5") (class "Default")
      (node (ref "C198") (pin "2") (pinfunction "2_2") (pintype "passive"))
      (node (ref "C199") (pin "1") (pinfunction "1_1") (pintype "passive"))
      (node (ref "C237") (pin "2") (pinfunction "2_2") (pintype "passive"))
      (node (ref "IC47") (pin "8") (pinfunction "VIN_8") (pintype "input"))
      (node (ref "L28") (pin "2") (pinfunction "2_2") (pintype "passive"))
    )
    (net (code "10") (name "/P5V5_N") (class "Default")
      (node (ref "C197") (pin "2") (pinfunction "2_2") (pintype "passive"))
      (node (ref "IC44") (pin "A1") (pinfunction "VOUT2_A1") (pintype "power_in"))
      (node (ref "IC44") (pin "B1") (pinfunction "VOUT2_B1") (pintype "power_in"))
      (node (ref "L28") (pin "1") (pinfunction "1_1") (pintype "passive"))
    )
    (net (code "11") (name "/PGOOD_VADJ") (class "Default")
      (node (ref "IC47") (pin "7") (pinfunction "PG_7") (pintype "open_collector"))
      (node (ref "IC49") (pin "3") (pinfunction "PG_3") (pintype "output"))
      (node (ref "J6") (pin "11") (pinfunction "11_11") (pintype "bidirectional"))
      (node (ref "T1") (pin "5") (pinfunction "G_5") (pintype "passive"))
    )
    (net (code "12") (name "/PG_1V8") (class "Default")
      (node (ref "IC43") (pin "5") (pinfunction "EN_5") (pintype "input"))
      (node (ref "IC47") (pin "5") (pinfunction "EN_5") (pintype "input"))
      (node (ref "IC48") (pin "5") (pinfunction "PG_5") (pintype "output"))
      (node (ref "IC49") (pin "2") (pinfunction "EN_2") (pintype "input"))
      (node (ref "R132") (pin "2") (pinfunction "2_2") (pintype "passive"))
    )
    (net (code "13") (name "/PG_3V7_5V5") (class "Default")
      (node (ref "IC44") (pin "B4") (pinfunction "PGOOD2_B4") (pintype "open_collector"))
      (node (ref "IC44") (pin "D4") (pinfunction "PGOOD1_D4") (pintype "open_collector"))
      (node (ref "IC46") (pin "1") (pinfunction "EN_1") (pintype "input"))
      (node (ref "R128") (pin "2") (pinfunction "2_2") (pintype "passive"))
    )
    (net (code "14") (name "/TEMP_ALARM") (class "Default")
      (node (ref "IC44") (pin "B2") (pinfunction "RUN2_B2") (pintype "input"))
      (node (ref "IC44") (pin "D2") (pinfunction "RUN1_D2") (pintype "input"))
      (node (ref "J6") (pin "9") (pinfunction "9_9") (pintype "bidirectional"))
    )
    (net (code "15") (name "GND") (class "Default")
      (node (ref "C185") (pin "1") (pinfunction "1_1") (pintype "passive"))
      (node (ref "C186") (pin "1") (pinfunction "1_1") (pintype "passive"))
      (node (ref "C187") (pin "2") (pinfunction "2_2") (pintype "passive"))
      (node (ref "C188") (pin "1") (pinfunction "1_1") (pintype "passive"))
      (node (ref "C189") (pin "1") (pinfunction "1_1") (pintype "passive"))
      (node (ref "C190") (pin "1") (pinfunction "1_1") (pintype "passive"))
      (node (ref "C193") (pin "1") (pinfunction "1_1") (pintype "passive"))
      (node (ref "C194") (pin "1") (pinfunction "1_1") (pintype "passive"))
      (node (ref "C195") (pin "1") (pinfunction "1_1") (pintype "passive"))
      (node (ref "C197") (pin "1") (pinfunction "1_1") (pintype "passive"))
      (node (ref "C198") (pin "1") (pinfunction "1_1") (pintype "passive"))
      (node (ref "C199") (pin "2") (pinfunction "2_2") (pintype "passive"))
      (node (ref "C200") (pin "1") (pinfunction "1_1") (pintype "passive"))
      (node (ref "C201") (pin "1") (pinfunction "1_1") (pintype "passive"))
      (node (ref "C206") (pin "1") (pinfunction "1_1") (pintype "passive"))
      (node (ref "C207") (pin "1") (pinfunction "1_1") (pintype "passive"))
      (node (ref "C231") (pin "1") (pinfunction "1_1") (pintype "passive"))
      (node (ref "C237") (pin "1") (pinfunction "1_1") (pintype "passive"))
      (node (ref "C257") (pin "1") (pinfunction "1_1") (pintype "passive"))
      (node (ref "C258") (pin "1") (pinfunction "1_1") (pintype "passive"))
      (node (ref "C259") (pin "1") (pinfunction "1_1") (pintype "passive"))
      (node (ref "C260") (pin "1") (pinfunction "1_1") (pintype "passive"))
      (node (ref "C261") (pin "2") (pinfunction "2_2") (pintype "passive"))
      (node (ref "C262") (pin "1") (pinfunction "1_1") (pintype "passive"))
      (node (ref "C264") (pin "1") (pinfunction "1_1") (pintype "passive"))
      (node (ref "C265") (pin "1") (pinfunction "1_1") (pintype "passive"))
      (node (ref "C266") (pin "1") (pinfunction "1_1") (pintype "passive"))
      (node (ref "C267") (pin "1") (pinfunction "1_1") (pintype "passive"))
      (node (ref "C268") (pin "1") (pinfunction "1_1") (pintype "passive"))
      (node (ref "C269") (pin "1") (pinfunction "1_1") (pintype "passive"))
      (node (ref "C270") (pin "1") (pinfunction "1_1") (pintype "passive"))
      (node (ref "C271") (pin "1") (pinfunction "1_1") (pintype "passive"))
      (node (ref "C272") (pin "1") (pinfunction "1_1") (pintype "passive"))
      (node (ref "IC43") (pin "6") (pinfunction "GND_6") (pintype "passive"))
      (node (ref "IC43") (pin "9") (pinfunction "EP_9") (pintype "passive"))
      (node (ref "IC44") (pin "B5") (pinfunction "GND_B5") (pintype "power_in"))
      (node (ref "IC44") (pin "C1") (pinfunction "GND_C1") (pintype "power_in"))
      (node (ref "IC44") (pin "C2") (pinfunction "GND_C2") (pintype "power_in"))
      (node (ref "IC44") (pin "C5") (pinfunction "SYNC/MODE_C5") (pintype "input"))
      (node (ref "IC44") (pin "D5") (pinfunction "GND_D5") (pintype "power_in"))
      (node (ref "IC45") (pin "6") (pinfunction "GND_6") (pintype "passive"))
      (node (ref "IC45") (pin "9") (pinfunction "EP_9") (pintype "passive"))
      (node (ref "IC46") (pin "2") (pinfunction "GND_2") (pintype "power_in"))
      (node (ref "IC47") (pin "3") (pinfunction "GND_3") (pintype "power_in"))
      (node (ref "IC47") (pin "6") (pinfunction "GND_6") (pintype "power_in"))
      (node (ref "IC47") (pin "9") (pinfunction "EPAD_9") (pintype "power_in"))
      (node (ref "IC48") (pin "17") (pinfunction "EP_17") (pintype "power_in"))
      (node (ref "IC48") (pin "6") (pinfunction "GND_6") (pintype "power_in"))
      (node (ref "IC49") (pin "10") (pinfunction "GND_10") (pintype "power_in"))
      (node (ref "IC49") (pin "13") (pinfunction "EP_13") (pintype "power_in"))
      (node (ref "IC49") (pin "9") (pinfunction "GND_9") (pintype "power_in"))
      (node (ref "J6") (pin "10") (pinfunction "10_10") (pintype "bidirectional"))
      (node (ref "J6") (pin "12") (pinfunction "12_12") (pintype "bidirectional"))
      (node (ref "J6") (pin "15") (pinfunction "15_15") (pintype "bidirectional"))
      (node (ref "J6") (pin "16") (pinfunction "16_16") (pintype "bidirectional"))
      (node (ref "J6") (pin "19") (pinfunction "19_19") (pintype "bidirectional"))
      (node (ref "J6") (pin "20") (pinfunction "20_20") (pintype "bidirectional"))
      (node (ref "J6") (pin "23") (pinfunction "23_23") (pintype "bidirectional"))
      (node (ref "J6") (pin "24") (pinfunction "24_24") (pintype "bidirectional"))
      (node (ref "J6") (pin "27") (pinfunction "27_27") (pintype "bidirectional"))
      (node (ref "J6") (pin "28") (pinfunction "28_28") (pintype "bidirectional"))
      (node (ref "J6") (pin "5") (pinfunction "5_5") (pintype "bidirectional"))
      (node (ref "J6") (pin "6") (pinfunction "6_6") (pintype "bidirectional"))
      (node (ref "LD5") (pin "1") (pinfunction "C_1") (pintype "passive"))
      (node (ref "LD6") (pin "1") (pinfunction "C_1") (pintype "passive"))
      (node (ref "R125") (pin "2") (pinfunction "2_2") (pintype "passive"))
      (node (ref "R127") (pin "2") (pinfunction "2_2") (pintype "passive"))
      (node (ref "R129") (pin "1") (pinfunction "1_1") (pintype "passive"))
      (node (ref "R131") (pin "1") (pinfunction "1_1") (pintype "passive"))
      (node (ref "R136") (pin "2") (pinfunction "2_2") (pintype "passive"))
      (node (ref "T1") (pin "4") (pinfunction "S_4") (pintype "passive"))
    )
    (net (code "16") (name "N3V0A") (class "Default")
      (node (ref "J6") (pin "7") (pinfunction "7_7") (pintype "bidirectional"))
      (node (ref "J6") (pin "8") (pinfunction "8_8") (pintype "bidirectional"))
      (node (ref "L36") (pin "2") (pinfunction "2_2") (pintype "passive"))
      (node (ref "TP32") (pin "1") (pinfunction "1_1") (pintype "bidirectional"))
    )
    (net (code "17") (name "Net-(C268-Pad2)") (class "Default")
      (node (ref "C268") (pin "2") (pinfunction "2_2") (pintype "passive"))
      (node (ref "C269") (pin "2") (pinfunction "2_2") (pintype "passive"))
      (node (ref "L35") (pin "2") (pinfunction "2_2") (pintype "passive"))
      (node (ref "L36") (pin "1") (pinfunction "1_1") (pintype "passive"))
    )
    (net (code "18") (name "Net-(IC43-SS)") (class "Default")
      (node (ref "C194") (pin "2") (pinfunction "2_2") (pintype "passive"))
      (node (ref "IC43") (pin "4") (pinfunction "SS_4") (pintype "input"))
    )
    (net (code "19") (name "Net-(IC44-COMP1)") (class "Default")
      (node (ref "IC44") (pin "E5") (pinfunction "COMP1_E5") (pintype "input"))
      (node (ref "TP25") (pin "1") (pinfunction "1_1") (pintype "bidirectional"))
    )
    (net (code "20") (name "Net-(IC44-COMP2)") (class "Default")
      (node (ref "IC44") (pin "A5") (pinfunction "COMP2_A5") (pintype "input"))
      (node (ref "TP26") (pin "1") (pinfunction "1_1") (pintype "bidirectional"))
    )
    (net (code "21") (name "Net-(IC44-FB1)") (class "Default")
      (node (ref "IC44") (pin "E4") (pinfunction "FB1_E4") (pintype "input"))
      (node (ref "R125") (pin "1") (pinfunction "1_1") (pintype "passive"))
    )
    (net (code "22") (name "Net-(IC44-FB2)") (class "Default")
      (node (ref "IC44") (pin "A4") (pinfunction "FB2_A4") (pintype "input"))
      (node (ref "R126") (pin "1") (pinfunction "1_1") (pintype "passive"))
    )
    (net (code "23") (name "Net-(IC44-FREQ)") (class "Default")
      (node (ref "IC44") (pin "C4") (pinfunction "FREQ_C4") (pintype "input"))
      (node (ref "R129") (pin "2") (pinfunction "2_2") (pintype "passive"))
    )
    (net (code "24") (name "Net-(IC44-INTVCC)") (class "Default")
      (node (ref "IC44") (pin "C3") (pinfunction "INTVCC_C3") (pintype "power_in"))
      (node (ref "TP27") (pin "1") (pinfunction "1_1") (pintype "bidirectional"))
    )
    (net (code "25") (name "Net-(IC44-TRACK{slash}SS1)") (class "Default")
      (node (ref "C195") (pin "2") (pinfunction "2_2") (pintype "passive"))
      (node (ref "IC44") (pin "A3") (pinfunction "TRACK/SS2_A3") (pintype "input"))
      (node (ref "IC44") (pin "E3") (pinfunction "TRACK/SS1_E3") (pintype "input"))
    )
    (net (code "26") (name "Net-(IC45-SS)") (class "Default")
      (node (ref "C206") (pin "2") (pinfunction "2_2") (pintype "passive"))
      (node (ref "IC45") (pin "4") (pinfunction "SS_4") (pintype "input"))
    )
    (net (code "27") (name "Net-(IC46-FB)") (class "Default")
      (node (ref "IC46") (pin "5") (pinfunction "FB_5") (pintype "input"))
      (node (ref "R130") (pin "1") (pinfunction "1_1") (pintype "passive"))
      (node (ref "R131") (pin "2") (pinfunction "2_2") (pintype "passive"))
    )
    (net (code "28") (name "Net-(IC46-SW)") (class "Default")
      (node (ref "IC46") (pin "3") (pinfunction "SW_3") (pintype "power_in"))
      (node (ref "L30") (pin "1") (pinfunction "1_1") (pintype "passive"))
    )
    (net (code "29") (name "Net-(IC47-SS)") (class "Default")
      (node (ref "C258") (pin "2") (pinfunction "2_2") (pintype "passive"))
      (node (ref "IC47") (pin "4") (pinfunction "SS_4") (pintype "input"))
    )
    (net (code "30") (name "Net-(IC48-SS)") (class "Default")
      (node (ref "C262") (pin "2") (pinfunction "2_2") (pintype "passive"))
      (node (ref "IC48") (pin "7") (pinfunction "SS_7") (pintype "input"))
    )
    (net (code "31") (name "Net-(IC49-CAP)") (class "Default")
      (node (ref "C270") (pin "2") (pinfunction "2_2") (pintype "passive"))
      (node (ref "IC49") (pin "6") (pinfunction "CAP_6") (pintype "output"))
    )
    (net (code "32") (name "Net-(IC49-CP)") (class "Default")
      (node (ref "C263") (pin "1") (pinfunction "1_1") (pintype "passive"))
      (node (ref "IC49") (pin "11") (pinfunction "CP_11") (pintype "output"))
    )
    (net (code "33") (name "Net-(IC49-FB)") (class "Default")
      (node (ref "IC49") (pin "5") (pinfunction "FB_5") (pintype "input"))
      (node (ref "R135") (pin "2") (pinfunction "2_2") (pintype "passive"))
      (node (ref "R136") (pin "1") (pinfunction "1_1") (pintype "passive"))
    )
    (net (code "34") (name "Net-(IC49-SW)") (class "Default")
      (node (ref "C263") (pin "2") (pinfunction "2_2") (pintype "passive"))
      (node (ref "IC49") (pin "8") (pinfunction "SW_8") (pintype "output"))
      (node (ref "L34") (pin "1") (pinfunction "1_1") (pintype "passive"))
    )
    (net (code "35") (name "Net-(IC49-VAUX)") (class "Default")
      (node (ref "C271") (pin "2") (pinfunction "2_2") (pintype "passive"))
      (node (ref "C272") (pin "2") (pinfunction "2_2") (pintype "passive"))
      (node (ref "IC49") (pin "1") (pinfunction "VAUX_1") (pintype "output"))
    )
    (net (code "36") (name "Net-(IC49-VIN)") (class "Default")
      (node (ref "C264") (pin "2") (pinfunction "2_2") (pintype "passive"))
      (node (ref "C265") (pin "2") (pinfunction "2_2") (pintype "passive"))
      (node (ref "IC49") (pin "12") (pinfunction "VIN_12") (pintype "input"))
      (node (ref "L33") (pin "1") (pinfunction "1_1") (pintype "passive"))
    )
    (net (code "37") (name "Net-(IC49-VREF)") (class "Default")
      (node (ref "IC49") (pin "4") (pinfunction "VREF_4") (pintype "output"))
      (node (ref "R135") (pin "1") (pinfunction "1_1") (pintype "passive"))
    )
    (net (code "38") (name "Net-(J6-Pad25)") (class "Default")
      (node (ref "J6") (pin "25") (pinfunction "25_25") (pintype "bidirectional"))
      (node (ref "TP33") (pin "1") (pinfunction "1_1") (pintype "bidirectional"))
    )
    (net (code "39") (name "Net-(J6-Pad26)") (class "Default")
      (node (ref "J6") (pin "26") (pinfunction "26_26") (pintype "bidirectional"))
      (node (ref "TP34") (pin "1") (pinfunction "1_1") (pintype "bidirectional"))
    )
    (net (code "40") (name "Net-(LD5-A)") (class "Default")
      (node (ref "LD5") (pin "2") (pinfunction "A_2") (pintype "passive"))
      (node (ref "R133") (pin "1") (pinfunction "1_1") (pintype "passive"))
    )
    (net (code "41") (name "Net-(LD6-A)") (class "Default")
      (node (ref "LD6") (pin "2") (pinfunction "A_2") (pintype "passive"))
      (node (ref "R134") (pin "1") (pinfunction "1_1") (pintype "passive"))
    )
    (net (code "42") (name "Net-(LD7-A)") (class "Default")
      (node (ref "LD7") (pin "2") (pinfunction "A_2") (pintype "passive"))
      (node (ref "R137") (pin "1") (pinfunction "1_1") (pintype "passive"))
    )
    (net (code "43") (name "Net-(LD7-C)") (class "Default")
      (node (ref "LD7") (pin "1") (pinfunction "C_1") (pintype "passive"))
      (node (ref "T1") (pin "3") (pinfunction "D_3") (pintype "passive"))
    )
    (net (code "44") (name "Net-(R126-Pad2)") (class "Default")
      (node (ref "R126") (pin "2") (pinfunction "2_2") (pintype "passive"))
      (node (ref "R127") (pin "1") (pinfunction "1_1") (pintype "passive"))
    )
    (net (code "45") (name "P1V8") (class "Default")
      (node (ref "C259") (pin "2") (pinfunction "2_2") (pintype "passive"))
      (node (ref "IC48") (pin "10") (pinfunction "VOUT_10") (pintype "power_in"))
      (node (ref "IC48") (pin "11") (pinfunction "VOUT_11") (pintype "power_in"))
      (node (ref "IC48") (pin "12") (pinfunction "VOUT_12") (pintype "power_in"))
      (node (ref "IC48") (pin "13") (pinfunction "VOUT_13") (pintype "power_in"))
      (node (ref "IC48") (pin "14") (pinfunction "VOUT_14") (pintype "power_in"))
      (node (ref "IC48") (pin "9") (pinfunction "SENS_9") (pintype "input"))
      (node (ref "J6") (pin "17") (pinfunction "17_17") (pintype "bidirectional"))
      (node (ref "J6") (pin "18") (pinfunction "18_18") (pintype "bidirectional"))
      (node (ref "TP31") (pin "1") (pinfunction "1_1") (pintype "bidirectional"))
    )
    (net (code "46") (name "P3V3") (class "Default")
      (node (ref "J6") (pin "21") (pinfunction "21_21") (pintype "bidirectional"))
      (node (ref "J6") (pin "22") (pinfunction "22_22") (pintype "bidirectional"))
      (node (ref "L33") (pin "2") (pinfunction "2_2") (pintype "passive"))
      (node (ref "R128") (pin "1") (pinfunction "1_1") (pintype "passive"))
      (node (ref "R132") (pin "1") (pinfunction "1_1") (pintype "passive"))
      (node (ref "R133") (pin "2") (pinfunction "2_2") (pintype "passive"))
      (node (ref "R137") (pin "2") (pinfunction "2_2") (pintype "passive"))
      (node (ref "TP29") (pin "1") (pinfunction "1_1") (pintype "bidirectional"))
    )
    (net (code "47") (name "P3V3A") (class "Default")
      (node (ref "J6") (pin "29") (pinfunction "29_29") (pintype "bidirectional"))
      (node (ref "J6") (pin "30") (pinfunction "30_30") (pintype "bidirectional"))
      (node (ref "L29") (pin "2") (pinfunction "2_2") (pintype "passive"))
    )
    (net (code "48") (name "P3V3_CLK") (class "Default")
      (node (ref "J6") (pin "1") (pinfunction "1_1") (pintype "bidirectional"))
      (node (ref "J6") (pin "2") (pinfunction "2_2") (pintype "bidirectional"))
      (node (ref "L21") (pin "2") (pinfunction "2_2") (pintype "passive"))
      (node (ref "TP30") (pin "1") (pinfunction "1_1") (pintype "bidirectional"))
    )
    (net (code "49") (name "P5V0A") (class "Default")
      (node (ref "J6") (pin "13") (pinfunction "13_13") (pintype "bidirectional"))
      (node (ref "J6") (pin "14") (pinfunction "14_14") (pintype "bidirectional"))
      (node (ref "L31") (pin "2") (pinfunction "2_2") (pintype "passive"))
      (node (ref "TP28") (pin "1") (pinfunction "1_1") (pintype "bidirectional"))
    )
    (net (code "50") (name "P12V0") (class "Default")
      (node (ref "C190") (pin "2") (pinfunction "2_2") (pintype "passive"))
      (node (ref "C193") (pin "2") (pinfunction "2_2") (pintype "passive"))
      (node (ref "C207") (pin "2") (pinfunction "2_2") (pintype "passive"))
      (node (ref "IC44") (pin "A2") (pinfunction "VIN1_A2") (pintype "power_in"))
      (node (ref "IC44") (pin "B3") (pinfunction "VIN1_B3") (pintype "power_in"))
      (node (ref "IC44") (pin "D3") (pinfunction "VIN2_D3") (pintype "power_in"))
      (node (ref "IC44") (pin "E2") (pinfunction "VIN2_E2") (pintype "power_in"))
      (node (ref "IC46") (pin "4") (pinfunction "VIN_4") (pintype "input"))
      (node (ref "J6") (pin "3") (pinfunction "3_3") (pintype "bidirectional"))
      (node (ref "J6") (pin "4") (pinfunction "4_4") (pintype "bidirectional"))
      (node (ref "R134") (pin "2") (pinfunction "2_2") (pintype "passive"))
    )
    (net (code "51") (name "unconnected-(B1-Pad1)") (class "Default")
      (node (ref "B1") (pin "1") (pinfunction "1_1") (pintype "bidirectional"))
    )
    (net (code "52") (name "unconnected-(B2-Pad1)") (class "Default")
      (node (ref "B2") (pin "1") (pinfunction "1_1") (pintype "bidirectional"))
    )
    (net (code "53") (name "unconnected-(IC48-NC-Pad8)") (class "Default")
      (node (ref "IC48") (pin "8") (pinfunction "NC_8") (pintype "passive"))
    )
    (net (code "54") (name "unconnected-(T1A-D-Pad6)") (class "Default")
      (node (ref "T1") (pin "6") (pinfunction "D_6") (pintype "passive+no_connect"))
    )
    (net (code "55") (name "unconnected-(T1A-G-Pad2)") (class "Default")
      (node (ref "T1") (pin "2") (pinfunction "G_2") (pintype "passive+no_connect"))
    )
    (net (code "56") (name "unconnected-(T1A-S-Pad1)") (class "Default")
      (node (ref "T1") (pin "1") (pinfunction "S_1") (pintype "passive+no_connect"))
    )
  )
)
